# hd-hdr.net
KiCad netlist of a schematic drawn in EAGLE
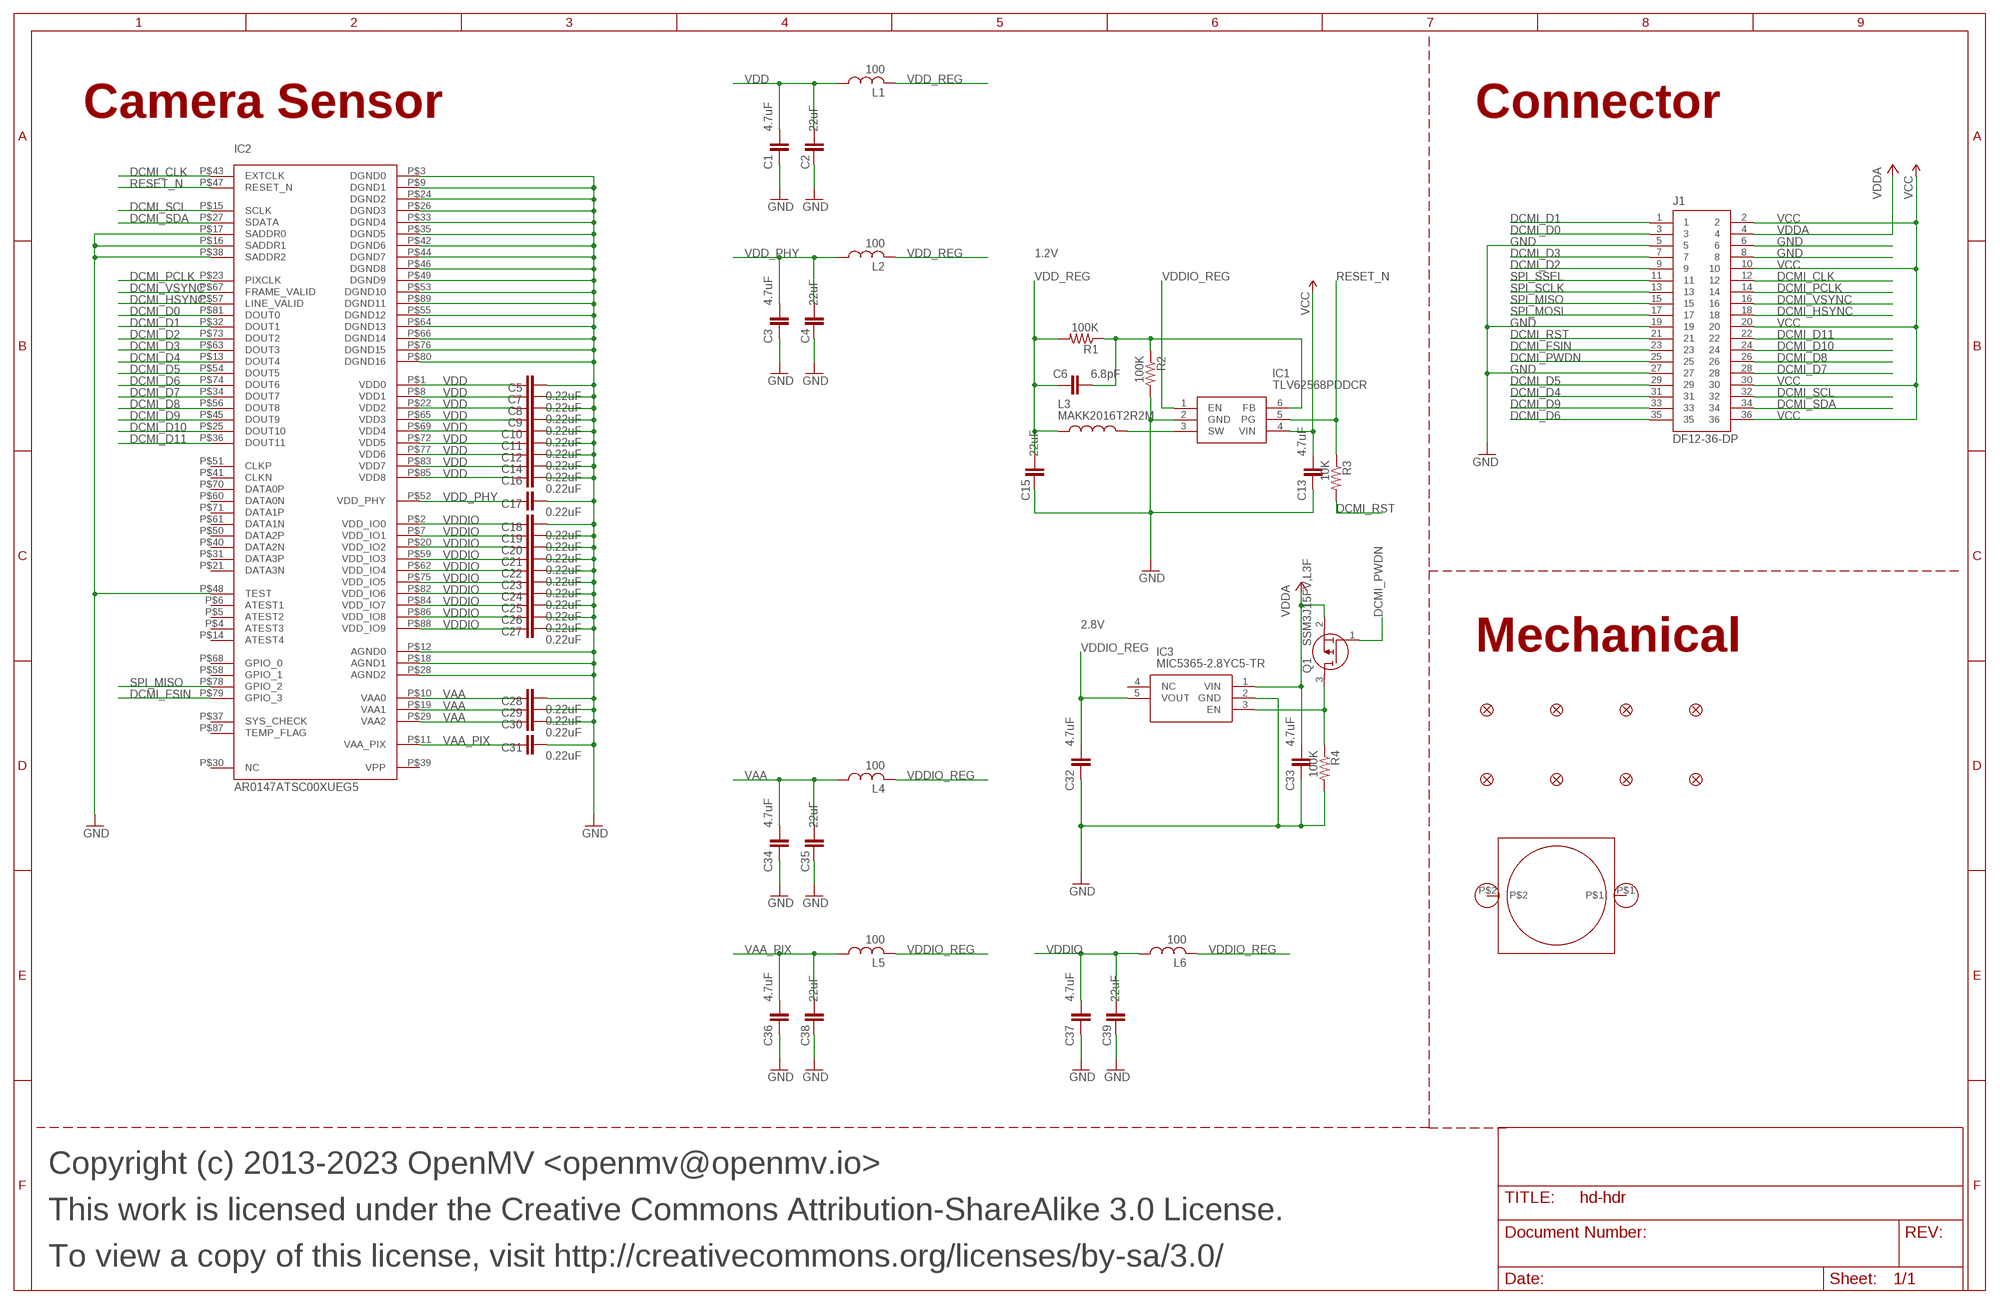
[diagram p0: schematic, sheet 1]

(export (version "E")
  (design (tool "Eeschema 10.0.6"))
  (components
    (comp (ref "C1")
      (value "4.7uF")
      (footprint "eagle-import:0402")
      (fields (field (name "MPN") "JMK105BBJ475MV-F"))
      (libsource (lib "eagle-import") (part "CAP_0402"))
    )
    (comp (ref "C2")
      (value "22uF")
      (footprint "eagle-import:0805")
      (fields (field (name "MPN") "CL21A226MQQNNNE"))
      (libsource (lib "eagle-import") (part "22UF-0805-6.3V-20%"))
    )
    (comp (ref "C3")
      (value "4.7uF")
      (footprint "eagle-import:0402")
      (fields (field (name "MPN") "JMK105BBJ475MV-F"))
      (libsource (lib "eagle-import") (part "CAP_0402"))
    )
    (comp (ref "C4")
      (value "22uF")
      (footprint "eagle-import:0805")
      (fields (field (name "MPN") "CL21A226MQQNNNE"))
      (libsource (lib "eagle-import") (part "22UF-0805-6.3V-20%"))
    )
    (comp (ref "C5")
      (value "0.22uF")
      (footprint "eagle-import:C0201")
      (fields (field (name "MPN") "GRM033R60J224ME15D"))
      (libsource (lib "eagle-import") (part "C-EUC0201"))
    )
    (comp (ref "C6")
      (value "6.8pF")
      (footprint "eagle-import:0402")
      (fields (field (name "MPN") "GRM1555C1H6R8DA01D"))
      (libsource (lib "eagle-import") (part "CAP_0402"))
    )
    (comp (ref "C7")
      (value "0.22uF")
      (footprint "eagle-import:C0201")
      (fields (field (name "MPN") "GRM033R60J224ME15D"))
      (libsource (lib "eagle-import") (part "C-EUC0201"))
    )
    (comp (ref "C8")
      (value "0.22uF")
      (footprint "eagle-import:C0201")
      (fields (field (name "MPN") "GRM033R60J224ME15D"))
      (libsource (lib "eagle-import") (part "C-EUC0201"))
    )
    (comp (ref "C9")
      (value "0.22uF")
      (footprint "eagle-import:C0201")
      (fields (field (name "MPN") "GRM033R60J224ME15D"))
      (libsource (lib "eagle-import") (part "C-EUC0201"))
    )
    (comp (ref "C10")
      (value "0.22uF")
      (footprint "eagle-import:C0201")
      (fields (field (name "MPN") "GRM033R60J224ME15D"))
      (libsource (lib "eagle-import") (part "C-EUC0201"))
    )
    (comp (ref "C11")
      (value "0.22uF")
      (footprint "eagle-import:C0201")
      (fields (field (name "MPN") "GRM033R60J224ME15D"))
      (libsource (lib "eagle-import") (part "C-EUC0201"))
    )
    (comp (ref "C12")
      (value "0.22uF")
      (footprint "eagle-import:C0201")
      (fields (field (name "MPN") "GRM033R60J224ME15D"))
      (libsource (lib "eagle-import") (part "C-EUC0201"))
    )
    (comp (ref "C13")
      (value "4.7uF")
      (footprint "eagle-import:0402")
      (fields (field (name "MPN") "JMK105BBJ475MV-F"))
      (libsource (lib "eagle-import") (part "CAP_0402"))
    )
    (comp (ref "C14")
      (value "0.22uF")
      (footprint "eagle-import:C0201")
      (fields (field (name "MPN") "GRM033R60J224ME15D"))
      (libsource (lib "eagle-import") (part "C-EUC0201"))
    )
    (comp (ref "C15")
      (value "22uF")
      (footprint "eagle-import:0805")
      (fields (field (name "MPN") "CL21A226MQQNNNE"))
      (libsource (lib "eagle-import") (part "22UF-0805-6.3V-20%"))
    )
    (comp (ref "C16")
      (value "0.22uF")
      (footprint "eagle-import:C0201")
      (fields (field (name "MPN") "GRM033R60J224ME15D"))
      (libsource (lib "eagle-import") (part "C-EUC0201"))
    )
    (comp (ref "C17")
      (value "0.22uF")
      (footprint "eagle-import:C0201")
      (fields (field (name "MPN") "GRM033R60J224ME15D"))
      (libsource (lib "eagle-import") (part "C-EUC0201"))
    )
    (comp (ref "C18")
      (value "0.22uF")
      (footprint "eagle-import:C0201")
      (fields (field (name "MPN") "GRM033R60J224ME15D"))
      (libsource (lib "eagle-import") (part "C-EUC0201"))
    )
    (comp (ref "C19")
      (value "0.22uF")
      (footprint "eagle-import:C0201")
      (fields (field (name "MPN") "GRM033R60J224ME15D"))
      (libsource (lib "eagle-import") (part "C-EUC0201"))
    )
    (comp (ref "C20")
      (value "0.22uF")
      (footprint "eagle-import:C0201")
      (fields (field (name "MPN") "GRM033R60J224ME15D"))
      (libsource (lib "eagle-import") (part "C-EUC0201"))
    )
    (comp (ref "C21")
      (value "0.22uF")
      (footprint "eagle-import:C0201")
      (fields (field (name "MPN") "GRM033R60J224ME15D"))
      (libsource (lib "eagle-import") (part "C-EUC0201"))
    )
    (comp (ref "C22")
      (value "0.22uF")
      (footprint "eagle-import:C0201")
      (fields (field (name "MPN") "GRM033R60J224ME15D"))
      (libsource (lib "eagle-import") (part "C-EUC0201"))
    )
    (comp (ref "C23")
      (value "0.22uF")
      (footprint "eagle-import:C0201")
      (fields (field (name "MPN") "GRM033R60J224ME15D"))
      (libsource (lib "eagle-import") (part "C-EUC0201"))
    )
    (comp (ref "C24")
      (value "0.22uF")
      (footprint "eagle-import:C0201")
      (fields (field (name "MPN") "GRM033R60J224ME15D"))
      (libsource (lib "eagle-import") (part "C-EUC0201"))
    )
    (comp (ref "C25")
      (value "0.22uF")
      (footprint "eagle-import:C0201")
      (fields (field (name "MPN") "GRM033R60J224ME15D"))
      (libsource (lib "eagle-import") (part "C-EUC0201"))
    )
    (comp (ref "C26")
      (value "0.22uF")
      (footprint "eagle-import:C0201")
      (fields (field (name "MPN") "GRM033R60J224ME15D"))
      (libsource (lib "eagle-import") (part "C-EUC0201"))
    )
    (comp (ref "C27")
      (value "0.22uF")
      (footprint "eagle-import:C0201")
      (fields (field (name "MPN") "GRM033R60J224ME15D"))
      (libsource (lib "eagle-import") (part "C-EUC0201"))
    )
    (comp (ref "C28")
      (value "0.22uF")
      (footprint "eagle-import:C0201")
      (fields (field (name "MPN") "GRM033R60J224ME15D"))
      (libsource (lib "eagle-import") (part "C-EUC0201"))
    )
    (comp (ref "C29")
      (value "0.22uF")
      (footprint "eagle-import:C0201")
      (fields (field (name "MPN") "GRM033R60J224ME15D"))
      (libsource (lib "eagle-import") (part "C-EUC0201"))
    )
    (comp (ref "C30")
      (value "0.22uF")
      (footprint "eagle-import:C0201")
      (fields (field (name "MPN") "GRM033R60J224ME15D"))
      (libsource (lib "eagle-import") (part "C-EUC0201"))
    )
    (comp (ref "C31")
      (value "0.22uF")
      (footprint "eagle-import:C0201")
      (fields (field (name "MPN") "GRM033R60J224ME15D"))
      (libsource (lib "eagle-import") (part "C-EUC0201"))
    )
    (comp (ref "C32")
      (value "4.7uF")
      (footprint "eagle-import:0402")
      (fields (field (name "MPN") "JMK105BBJ475MV-F"))
      (libsource (lib "eagle-import") (part "CAP_0402"))
    )
    (comp (ref "C33")
      (value "4.7uF")
      (footprint "eagle-import:0402")
      (fields (field (name "MPN") "JMK105BBJ475MV-F"))
      (libsource (lib "eagle-import") (part "CAP_0402"))
    )
    (comp (ref "C34")
      (value "4.7uF")
      (footprint "eagle-import:0402")
      (fields (field (name "MPN") "JMK105BBJ475MV-F"))
      (libsource (lib "eagle-import") (part "CAP_0402"))
    )
    (comp (ref "C35")
      (value "22uF")
      (footprint "eagle-import:0805")
      (fields (field (name "MPN") "CL21A226MQQNNNE"))
      (libsource (lib "eagle-import") (part "22UF-0805-6.3V-20%"))
    )
    (comp (ref "C36")
      (value "4.7uF")
      (footprint "eagle-import:0402")
      (fields (field (name "MPN") "JMK105BBJ475MV-F"))
      (libsource (lib "eagle-import") (part "CAP_0402"))
    )
    (comp (ref "C37")
      (value "4.7uF")
      (footprint "eagle-import:0402")
      (fields (field (name "MPN") "JMK105BBJ475MV-F"))
      (libsource (lib "eagle-import") (part "CAP_0402"))
    )
    (comp (ref "C38")
      (value "22uF")
      (footprint "eagle-import:0805")
      (fields (field (name "MPN") "CL21A226MQQNNNE"))
      (libsource (lib "eagle-import") (part "22UF-0805-6.3V-20%"))
    )
    (comp (ref "C39")
      (value "22uF")
      (footprint "eagle-import:0805")
      (fields (field (name "MPN") "CL21A226MQQNNNE"))
      (libsource (lib "eagle-import") (part "22UF-0805-6.3V-20%"))
    )
    (comp (ref "FD1")
      (value "FIDUCIAL1X2")
      (footprint "eagle-import:FIDUCIAL-1X2")
      (libsource (lib "eagle-import") (part "FIDUCIAL1X2"))
    )
    (comp (ref "FD2")
      (value "FIDUCIAL1X2")
      (footprint "eagle-import:FIDUCIAL-1X2")
      (libsource (lib "eagle-import") (part "FIDUCIAL1X2"))
    )
    (comp (ref "FD3")
      (value "FIDUCIAL1X2")
      (footprint "eagle-import:FIDUCIAL-1X2")
      (libsource (lib "eagle-import") (part "FIDUCIAL1X2"))
    )
    (comp (ref "FD4")
      (value "FIDUCIAL1X2")
      (footprint "eagle-import:FIDUCIAL-1X2")
      (libsource (lib "eagle-import") (part "FIDUCIAL1X2"))
    )
    (comp (ref "FD5")
      (value "FIDUCIAL1X2")
      (footprint "eagle-import:FIDUCIAL-1X2")
      (libsource (lib "eagle-import") (part "FIDUCIAL1X2"))
    )
    (comp (ref "FD6")
      (value "FIDUCIAL1X2")
      (footprint "eagle-import:FIDUCIAL-1X2")
      (libsource (lib "eagle-import") (part "FIDUCIAL1X2"))
    )
    (comp (ref "FD7")
      (value "FIDUCIAL1X2")
      (footprint "eagle-import:FIDUCIAL-1X2")
      (libsource (lib "eagle-import") (part "FIDUCIAL1X2"))
    )
    (comp (ref "FD8")
      (value "FIDUCIAL1X2")
      (footprint "eagle-import:FIDUCIAL-1X2")
      (libsource (lib "eagle-import") (part "FIDUCIAL1X2"))
    )
    (comp (ref "H1")
      (value "LENSMOUNT20MM")
      (footprint "eagle-import:LENSMOUNT-20MM")
      (libsource (lib "eagle-import") (part "LENSMOUNT20MM"))
    )
    (comp (ref "IC1")
      (value "TLV62568PDDCR")
      (footprint "eagle-import:SOT95P280X110-6N")
      (fields (field (name "MOUSER_PART_NUMBER") "595-TLV62568PDDCR"))
      (libsource (lib "eagle-import") (part "TLV62568PDDCR"))
    )
    (comp (ref "IC2")
      (value "AR0147ATSC00XUEG5")
      (footprint "eagle-import:AR0147ATSC00XUEG5")
      (fields (field (name "MPN") "AR0147ATSC00XUEG5-DRBR"))
      (libsource (lib "eagle-import") (part "AR0147ATSC00XUEG5"))
    )
    (comp (ref "IC3")
      (value "MIC5365-2.8YC5-TR")
      (footprint "eagle-import:SOT65P210X110-5N")
      (fields (field (name "MOUSER_PART_NUMBER") "998-MIC5365-2.8YC5TR"))
      (libsource (lib "eagle-import") (part "MIC5365-2.8YC5-TR"))
    )
    (comp (ref "J1")
      (value "DF12-36-DP")
      (footprint "eagle-import:DF12-36-DP")
      (fields (field (name "MPN") "DF12NB(3.0)-36DP-0.5V(51)"))
      (libsource (lib "eagle-import") (part "DF12-36-DP"))
    )
    (comp (ref "L1")
      (value "100")
      (footprint "eagle-import:0402")
      (fields (field (name "MPN") "MFBM1V1005-101-R"))
      (libsource (lib "eagle-import") (part "INDUCTOR_0402"))
    )
    (comp (ref "L2")
      (value "100")
      (footprint "eagle-import:0402")
      (fields (field (name "MPN") "MFBM1V1005-101-R"))
      (libsource (lib "eagle-import") (part "INDUCTOR_0402"))
    )
    (comp (ref "L3")
      (value "MAKK2016T2R2M")
      (footprint "eagle-import:INDC2016X100N")
      (fields (field (name "MF") "Taiyo Yuden"))
      (libsource (lib "eagle-import") (part "MAKK2016T2R2M"))
    )
    (comp (ref "L4")
      (value "100")
      (footprint "eagle-import:0402")
      (fields (field (name "MPN") "MFBM1V1005-101-R"))
      (libsource (lib "eagle-import") (part "INDUCTOR_0402"))
    )
    (comp (ref "L5")
      (value "100")
      (footprint "eagle-import:0402")
      (fields (field (name "MPN") "MFBM1V1005-101-R"))
      (libsource (lib "eagle-import") (part "INDUCTOR_0402"))
    )
    (comp (ref "L6")
      (value "100")
      (footprint "eagle-import:0402")
      (fields (field (name "MPN") "MFBM1V1005-101-R"))
      (libsource (lib "eagle-import") (part "INDUCTOR_0402"))
    )
    (comp (ref "Q1")
      (value "SSM3J15FV,L3F")
      (footprint "eagle-import:SSM3J15FVL3F")
      (fields (field (name "MOUSER_PART_NUMBER") "757-SSM3J15FVL3F"))
      (libsource (lib "eagle-import") (part "SSM3J15FV,L3F"))
    )
    (comp (ref "R1")
      (value "100K")
      (footprint "eagle-import:R0402")
      (fields (field (name "MPN") "AC0402FR-07100KL"))
      (libsource (lib "eagle-import") (part "R-US_R0402"))
    )
    (comp (ref "R2")
      (value "100K")
      (footprint "eagle-import:R0402")
      (fields (field (name "MPN") "AC0402FR-07100KL"))
      (libsource (lib "eagle-import") (part "R-US_R0402"))
    )
    (comp (ref "R3")
      (value "10K")
      (footprint "eagle-import:R0402")
      (fields (field (name "MPN") "AC0402FR-1310KL"))
      (libsource (lib "eagle-import") (part "R-US_R0402"))
    )
    (comp (ref "R4")
      (value "100K")
      (footprint "eagle-import:R0402")
      (fields (field (name "MPN") "AC0402FR-07100KL"))
      (libsource (lib "eagle-import") (part "R-US_R0402"))
    )
  )
  (nets
    (net (code "1") (name "/DCMI_CLK") (class "Default")
      (node (ref "IC2") (pin "P$43") (pinfunction "EXTCLK_P$43") (pintype "bidirectional"))
      (node (ref "J1") (pin "12") (pinfunction "12_12") (pintype "bidirectional"))
    )
    (net (code "2") (name "/DCMI_D0") (class "Default")
      (node (ref "IC2") (pin "P$81") (pinfunction "DOUT0_P$81") (pintype "bidirectional"))
      (node (ref "J1") (pin "3") (pinfunction "3_3") (pintype "bidirectional"))
    )
    (net (code "3") (name "/DCMI_D1") (class "Default")
      (node (ref "IC2") (pin "P$32") (pinfunction "DOUT1_P$32") (pintype "bidirectional"))
      (node (ref "J1") (pin "1") (pinfunction "1_1") (pintype "bidirectional"))
    )
    (net (code "4") (name "/DCMI_D2") (class "Default")
      (node (ref "IC2") (pin "P$73") (pinfunction "DOUT2_P$73") (pintype "bidirectional"))
      (node (ref "J1") (pin "9") (pinfunction "9_9") (pintype "bidirectional"))
    )
    (net (code "5") (name "/DCMI_D3") (class "Default")
      (node (ref "IC2") (pin "P$63") (pinfunction "DOUT3_P$63") (pintype "bidirectional"))
      (node (ref "J1") (pin "7") (pinfunction "7_7") (pintype "bidirectional"))
    )
    (net (code "6") (name "/DCMI_D4") (class "Default")
      (node (ref "IC2") (pin "P$13") (pinfunction "DOUT4_P$13") (pintype "bidirectional"))
      (node (ref "J1") (pin "31") (pinfunction "31_31") (pintype "bidirectional"))
    )
    (net (code "7") (name "/DCMI_D5") (class "Default")
      (node (ref "IC2") (pin "P$54") (pinfunction "DOUT5_P$54") (pintype "bidirectional"))
      (node (ref "J1") (pin "29") (pinfunction "29_29") (pintype "bidirectional"))
    )
    (net (code "8") (name "/DCMI_D6") (class "Default")
      (node (ref "IC2") (pin "P$74") (pinfunction "DOUT6_P$74") (pintype "bidirectional"))
      (node (ref "J1") (pin "35") (pinfunction "35_35") (pintype "bidirectional"))
    )
    (net (code "9") (name "/DCMI_D7") (class "Default")
      (node (ref "IC2") (pin "P$34") (pinfunction "DOUT7_P$34") (pintype "bidirectional"))
      (node (ref "J1") (pin "28") (pinfunction "28_28") (pintype "bidirectional"))
    )
    (net (code "10") (name "/DCMI_D8") (class "Default")
      (node (ref "IC2") (pin "P$56") (pinfunction "DOUT8_P$56") (pintype "bidirectional"))
      (node (ref "J1") (pin "26") (pinfunction "26_26") (pintype "bidirectional"))
    )
    (net (code "11") (name "/DCMI_D9") (class "Default")
      (node (ref "IC2") (pin "P$45") (pinfunction "DOUT9_P$45") (pintype "bidirectional"))
      (node (ref "J1") (pin "33") (pinfunction "33_33") (pintype "bidirectional"))
    )
    (net (code "12") (name "/DCMI_D10") (class "Default")
      (node (ref "IC2") (pin "P$25") (pinfunction "DOUT10_P$25") (pintype "bidirectional"))
      (node (ref "J1") (pin "24") (pinfunction "24_24") (pintype "bidirectional"))
    )
    (net (code "13") (name "/DCMI_D11") (class "Default")
      (node (ref "IC2") (pin "P$36") (pinfunction "DOUT11_P$36") (pintype "bidirectional"))
      (node (ref "J1") (pin "22") (pinfunction "22_22") (pintype "bidirectional"))
    )
    (net (code "14") (name "/DCMI_FSIN") (class "Default")
      (node (ref "IC2") (pin "P$79") (pinfunction "GPIO_3_P$79") (pintype "bidirectional"))
      (node (ref "J1") (pin "23") (pinfunction "23_23") (pintype "bidirectional"))
    )
    (net (code "15") (name "/DCMI_HSYNC") (class "Default")
      (node (ref "IC2") (pin "P$57") (pinfunction "LINE_VALID_P$57") (pintype "bidirectional"))
      (node (ref "J1") (pin "18") (pinfunction "18_18") (pintype "bidirectional"))
    )
    (net (code "16") (name "/DCMI_PCLK") (class "Default")
      (node (ref "IC2") (pin "P$23") (pinfunction "PIXCLK_P$23") (pintype "bidirectional"))
      (node (ref "J1") (pin "14") (pinfunction "14_14") (pintype "bidirectional"))
    )
    (net (code "17") (name "/DCMI_PWDN") (class "Default")
      (node (ref "J1") (pin "25") (pinfunction "25_25") (pintype "bidirectional"))
      (node (ref "Q1") (pin "1") (pinfunction "G_1") (pintype "bidirectional"))
    )
    (net (code "18") (name "/DCMI_RST") (class "Default")
      (node (ref "J1") (pin "21") (pinfunction "21_21") (pintype "bidirectional"))
      (node (ref "R3") (pin "2") (pinfunction "2_2") (pintype "passive"))
    )
    (net (code "19") (name "/DCMI_SCL") (class "Default")
      (node (ref "IC2") (pin "P$15") (pinfunction "SCLK_P$15") (pintype "bidirectional"))
      (node (ref "J1") (pin "32") (pinfunction "32_32") (pintype "bidirectional"))
    )
    (net (code "20") (name "/DCMI_SDA") (class "Default")
      (node (ref "IC2") (pin "P$27") (pinfunction "SDATA_P$27") (pintype "bidirectional"))
      (node (ref "J1") (pin "34") (pinfunction "34_34") (pintype "bidirectional"))
    )
    (net (code "21") (name "/DCMI_VSYNC") (class "Default")
      (node (ref "IC2") (pin "P$67") (pinfunction "FRAME_VALID_P$67") (pintype "bidirectional"))
      (node (ref "J1") (pin "16") (pinfunction "16_16") (pintype "bidirectional"))
    )
    (net (code "22") (name "/P$1") (class "Default")
      (node (ref "H1") (pin "P$1") (pinfunction "P$1_P$1") (pintype "power_in"))
    )
    (net (code "23") (name "/P$2") (class "Default")
      (node (ref "H1") (pin "P$2") (pinfunction "P$2_P$2") (pintype "power_in"))
    )
    (net (code "24") (name "/RESET_N") (class "Default")
      (node (ref "IC1") (pin "5") (pinfunction "PG_5") (pintype "bidirectional"))
      (node (ref "IC2") (pin "P$47") (pinfunction "RESET_N_P$47") (pintype "bidirectional"))
      (node (ref "R3") (pin "1") (pinfunction "1_1") (pintype "passive"))
    )
    (net (code "25") (name "/SPI_MISO") (class "Default")
      (node (ref "IC2") (pin "P$78") (pinfunction "GPIO_2_P$78") (pintype "bidirectional"))
      (node (ref "J1") (pin "15") (pinfunction "15_15") (pintype "bidirectional"))
    )
    (net (code "26") (name "/SPI_MOSI") (class "Default")
      (node (ref "J1") (pin "17") (pinfunction "17_17") (pintype "bidirectional"))
    )
    (net (code "27") (name "/SPI_SCLK") (class "Default")
      (node (ref "J1") (pin "13") (pinfunction "13_13") (pintype "bidirectional"))
    )
    (net (code "28") (name "/SPI_SSEL") (class "Default")
      (node (ref "J1") (pin "11") (pinfunction "11_11") (pintype "bidirectional"))
    )
    (net (code "29") (name "/VAA") (class "Default")
      (node (ref "C28") (pin "1") (pinfunction "1_1") (pintype "passive"))
      (node (ref "C29") (pin "1") (pinfunction "1_1") (pintype "passive"))
      (node (ref "C30") (pin "1") (pinfunction "1_1") (pintype "passive"))
      (node (ref "C34") (pin "2") (pinfunction "2_2") (pintype "passive"))
      (node (ref "C35") (pin "2") (pinfunction "2_2") (pintype "passive"))
      (node (ref "IC2") (pin "P$10") (pinfunction "VAA0_P$10") (pintype "bidirectional"))
      (node (ref "IC2") (pin "P$19") (pinfunction "VAA1_P$19") (pintype "bidirectional"))
      (node (ref "IC2") (pin "P$29") (pinfunction "VAA2_P$29") (pintype "bidirectional"))
      (node (ref "L4") (pin "1") (pinfunction "P$1_1") (pintype "passive"))
    )
    (net (code "30") (name "/VAA_PIX") (class "Default")
      (node (ref "C31") (pin "1") (pinfunction "1_1") (pintype "passive"))
      (node (ref "C36") (pin "2") (pinfunction "2_2") (pintype "passive"))
      (node (ref "C38") (pin "2") (pinfunction "2_2") (pintype "passive"))
      (node (ref "IC2") (pin "P$11") (pinfunction "VAA_PIX_P$11") (pintype "bidirectional"))
      (node (ref "L5") (pin "1") (pinfunction "P$1_1") (pintype "passive"))
    )
    (net (code "31") (name "/VDD") (class "Default")
      (node (ref "C1") (pin "2") (pinfunction "2_2") (pintype "passive"))
      (node (ref "C10") (pin "1") (pinfunction "1_1") (pintype "passive"))
      (node (ref "C11") (pin "1") (pinfunction "1_1") (pintype "passive"))
      (node (ref "C12") (pin "1") (pinfunction "1_1") (pintype "passive"))
      (node (ref "C14") (pin "1") (pinfunction "1_1") (pintype "passive"))
      (node (ref "C16") (pin "1") (pinfunction "1_1") (pintype "passive"))
      (node (ref "C2") (pin "2") (pinfunction "2_2") (pintype "passive"))
      (node (ref "C5") (pin "1") (pinfunction "1_1") (pintype "passive"))
      (node (ref "C7") (pin "1") (pinfunction "1_1") (pintype "passive"))
      (node (ref "C8") (pin "1") (pinfunction "1_1") (pintype "passive"))
      (node (ref "C9") (pin "1") (pinfunction "1_1") (pintype "passive"))
      (node (ref "IC2") (pin "P$1") (pinfunction "VDD0_P$1") (pintype "bidirectional"))
      (node (ref "IC2") (pin "P$22") (pinfunction "VDD2_P$22") (pintype "bidirectional"))
      (node (ref "IC2") (pin "P$65") (pinfunction "VDD3_P$65") (pintype "bidirectional"))
      (node (ref "IC2") (pin "P$69") (pinfunction "VDD4_P$69") (pintype "bidirectional"))
      (node (ref "IC2") (pin "P$72") (pinfunction "VDD5_P$72") (pintype "bidirectional"))
      (node (ref "IC2") (pin "P$77") (pinfunction "VDD6_P$77") (pintype "bidirectional"))
      (node (ref "IC2") (pin "P$8") (pinfunction "VDD1_P$8") (pintype "bidirectional"))
      (node (ref "IC2") (pin "P$83") (pinfunction "VDD7_P$83") (pintype "bidirectional"))
      (node (ref "IC2") (pin "P$85") (pinfunction "VDD8_P$85") (pintype "bidirectional"))
      (node (ref "L1") (pin "1") (pinfunction "P$1_1") (pintype "passive"))
    )
    (net (code "32") (name "/VDDIO") (class "Default")
      (node (ref "C18") (pin "1") (pinfunction "1_1") (pintype "passive"))
      (node (ref "C19") (pin "1") (pinfunction "1_1") (pintype "passive"))
      (node (ref "C20") (pin "1") (pinfunction "1_1") (pintype "passive"))
      (node (ref "C21") (pin "1") (pinfunction "1_1") (pintype "passive"))
      (node (ref "C22") (pin "1") (pinfunction "1_1") (pintype "passive"))
      (node (ref "C23") (pin "1") (pinfunction "1_1") (pintype "passive"))
      (node (ref "C24") (pin "1") (pinfunction "1_1") (pintype "passive"))
      (node (ref "C25") (pin "1") (pinfunction "1_1") (pintype "passive"))
      (node (ref "C26") (pin "1") (pinfunction "1_1") (pintype "passive"))
      (node (ref "C27") (pin "1") (pinfunction "1_1") (pintype "passive"))
      (node (ref "C37") (pin "2") (pinfunction "2_2") (pintype "passive"))
      (node (ref "C39") (pin "2") (pinfunction "2_2") (pintype "passive"))
      (node (ref "IC2") (pin "P$2") (pinfunction "VDD_IO0_P$2") (pintype "bidirectional"))
      (node (ref "IC2") (pin "P$20") (pinfunction "VDD_IO2_P$20") (pintype "bidirectional"))
      (node (ref "IC2") (pin "P$59") (pinfunction "VDD_IO3_P$59") (pintype "bidirectional"))
      (node (ref "IC2") (pin "P$62") (pinfunction "VDD_IO4_P$62") (pintype "bidirectional"))
      (node (ref "IC2") (pin "P$7") (pinfunction "VDD_IO1_P$7") (pintype "bidirectional"))
      (node (ref "IC2") (pin "P$75") (pinfunction "VDD_IO5_P$75") (pintype "bidirectional"))
      (node (ref "IC2") (pin "P$82") (pinfunction "VDD_IO6_P$82") (pintype "bidirectional"))
      (node (ref "IC2") (pin "P$84") (pinfunction "VDD_IO7_P$84") (pintype "bidirectional"))
      (node (ref "IC2") (pin "P$86") (pinfunction "VDD_IO8_P$86") (pintype "bidirectional"))
      (node (ref "IC2") (pin "P$88") (pinfunction "VDD_IO9_P$88") (pintype "bidirectional"))
      (node (ref "L6") (pin "1") (pinfunction "P$1_1") (pintype "passive"))
    )
    (net (code "33") (name "/VDDIO_REG") (class "Default")
      (node (ref "C32") (pin "2") (pinfunction "2_2") (pintype "passive"))
      (node (ref "IC1") (pin "1") (pinfunction "EN_1") (pintype "bidirectional"))
      (node (ref "IC3") (pin "5") (pinfunction "VOUT_5") (pintype "bidirectional"))
      (node (ref "L4") (pin "2") (pinfunction "P$2_2") (pintype "passive"))
      (node (ref "L5") (pin "2") (pinfunction "P$2_2") (pintype "passive"))
      (node (ref "L6") (pin "2") (pinfunction "P$2_2") (pintype "passive"))
    )
    (net (code "34") (name "/VDD_PHY") (class "Default")
      (node (ref "C17") (pin "1") (pinfunction "1_1") (pintype "passive"))
      (node (ref "C3") (pin "2") (pinfunction "2_2") (pintype "passive"))
      (node (ref "C4") (pin "2") (pinfunction "2_2") (pintype "passive"))
      (node (ref "IC2") (pin "P$52") (pinfunction "VDD_PHY_P$52") (pintype "bidirectional"))
      (node (ref "L2") (pin "1") (pinfunction "P$1_1") (pintype "passive"))
    )
    (net (code "35") (name "/VDD_REG") (class "Default")
      (node (ref "C15") (pin "2") (pinfunction "2_2") (pintype "passive"))
      (node (ref "C6") (pin "1") (pinfunction "1_1") (pintype "passive"))
      (node (ref "L1") (pin "2") (pinfunction "P$2_2") (pintype "passive"))
      (node (ref "L2") (pin "2") (pinfunction "P$2_2") (pintype "passive"))
      (node (ref "L3") (pin "1") (pinfunction "1_1") (pintype "passive"))
      (node (ref "R1") (pin "2") (pinfunction "2_2") (pintype "passive"))
    )
    (net (code "36") (name "GND") (class "Default")
      (node (ref "C1") (pin "1") (pinfunction "1_1") (pintype "passive"))
      (node (ref "C10") (pin "2") (pinfunction "2_2") (pintype "passive"))
      (node (ref "C11") (pin "2") (pinfunction "2_2") (pintype "passive"))
      (node (ref "C12") (pin "2") (pinfunction "2_2") (pintype "passive"))
      (node (ref "C13") (pin "1") (pinfunction "1_1") (pintype "passive"))
      (node (ref "C14") (pin "2") (pinfunction "2_2") (pintype "passive"))
      (node (ref "C15") (pin "1") (pinfunction "1_1") (pintype "passive"))
      (node (ref "C16") (pin "2") (pinfunction "2_2") (pintype "passive"))
      (node (ref "C17") (pin "2") (pinfunction "2_2") (pintype "passive"))
      (node (ref "C18") (pin "2") (pinfunction "2_2") (pintype "passive"))
      (node (ref "C19") (pin "2") (pinfunction "2_2") (pintype "passive"))
      (node (ref "C2") (pin "1") (pinfunction "1_1") (pintype "passive"))
      (node (ref "C20") (pin "2") (pinfunction "2_2") (pintype "passive"))
      (node (ref "C21") (pin "2") (pinfunction "2_2") (pintype "passive"))
      (node (ref "C22") (pin "2") (pinfunction "2_2") (pintype "passive"))
      (node (ref "C23") (pin "2") (pinfunction "2_2") (pintype "passive"))
      (node (ref "C24") (pin "2") (pinfunction "2_2") (pintype "passive"))
      (node (ref "C25") (pin "2") (pinfunction "2_2") (pintype "passive"))
      (node (ref "C26") (pin "2") (pinfunction "2_2") (pintype "passive"))
      (node (ref "C27") (pin "2") (pinfunction "2_2") (pintype "passive"))
      (node (ref "C28") (pin "2") (pinfunction "2_2") (pintype "passive"))
      (node (ref "C29") (pin "2") (pinfunction "2_2") (pintype "passive"))
      (node (ref "C3") (pin "1") (pinfunction "1_1") (pintype "passive"))
      (node (ref "C30") (pin "2") (pinfunction "2_2") (pintype "passive"))
      (node (ref "C31") (pin "2") (pinfunction "2_2") (pintype "passive"))
      (node (ref "C32") (pin "1") (pinfunction "1_1") (pintype "passive"))
      (node (ref "C33") (pin "1") (pinfunction "1_1") (pintype "passive"))
      (node (ref "C34") (pin "1") (pinfunction "1_1") (pintype "passive"))
      (node (ref "C35") (pin "1") (pinfunction "1_1") (pintype "passive"))
      (node (ref "C36") (pin "1") (pinfunction "1_1") (pintype "passive"))
      (node (ref "C37") (pin "1") (pinfunction "1_1") (pintype "passive"))
      (node (ref "C38") (pin "1") (pinfunction "1_1") (pintype "passive"))
      (node (ref "C39") (pin "1") (pinfunction "1_1") (pintype "passive"))
      (node (ref "C4") (pin "1") (pinfunction "1_1") (pintype "passive"))
      (node (ref "C5") (pin "2") (pinfunction "2_2") (pintype "passive"))
      (node (ref "C7") (pin "2") (pinfunction "2_2") (pintype "passive"))
      (node (ref "C8") (pin "2") (pinfunction "2_2") (pintype "passive"))
      (node (ref "C9") (pin "2") (pinfunction "2_2") (pintype "passive"))
      (node (ref "IC1") (pin "2") (pinfunction "GND_2") (pintype "bidirectional"))
      (node (ref "IC2") (pin "P$12") (pinfunction "AGND0_P$12") (pintype "bidirectional"))
      (node (ref "IC2") (pin "P$16") (pinfunction "SADDR1_P$16") (pintype "bidirectional"))
      (node (ref "IC2") (pin "P$17") (pinfunction "SADDR0_P$17") (pintype "bidirectional"))
      (node (ref "IC2") (pin "P$18") (pinfunction "AGND1_P$18") (pintype "bidirectional"))
      (node (ref "IC2") (pin "P$24") (pinfunction "DGND2_P$24") (pintype "bidirectional"))
      (node (ref "IC2") (pin "P$26") (pinfunction "DGND3_P$26") (pintype "bidirectional"))
      (node (ref "IC2") (pin "P$28") (pinfunction "AGND2_P$28") (pintype "bidirectional"))
      (node (ref "IC2") (pin "P$3") (pinfunction "DGND0_P$3") (pintype "bidirectional"))
      (node (ref "IC2") (pin "P$33") (pinfunction "DGND4_P$33") (pintype "bidirectional"))
      (node (ref "IC2") (pin "P$35") (pinfunction "DGND5_P$35") (pintype "bidirectional"))
      (node (ref "IC2") (pin "P$38") (pinfunction "SADDR2_P$38") (pintype "bidirectional"))
      (node (ref "IC2") (pin "P$42") (pinfunction "DGND6_P$42") (pintype "bidirectional"))
      (node (ref "IC2") (pin "P$44") (pinfunction "DGND7_P$44") (pintype "bidirectional"))
      (node (ref "IC2") (pin "P$46") (pinfunction "DGND8_P$46") (pintype "bidirectional"))
      (node (ref "IC2") (pin "P$48") (pinfunction "TEST_P$48") (pintype "bidirectional"))
      (node (ref "IC2") (pin "P$49") (pinfunction "DGND9_P$49") (pintype "bidirectional"))
      (node (ref "IC2") (pin "P$53") (pinfunction "DGND10_P$53") (pintype "bidirectional"))
      (node (ref "IC2") (pin "P$55") (pinfunction "DGND12_P$55") (pintype "bidirectional"))
      (node (ref "IC2") (pin "P$64") (pinfunction "DGND13_P$64") (pintype "bidirectional"))
      (node (ref "IC2") (pin "P$66") (pinfunction "DGND14_P$66") (pintype "bidirectional"))
      (node (ref "IC2") (pin "P$76") (pinfunction "DGND15_P$76") (pintype "bidirectional"))
      (node (ref "IC2") (pin "P$80") (pinfunction "DGND16_P$80") (pintype "bidirectional"))
      (node (ref "IC2") (pin "P$89") (pinfunction "DGND11_P$89") (pintype "bidirectional"))
      (node (ref "IC2") (pin "P$9") (pinfunction "DGND1_P$9") (pintype "bidirectional"))
      (node (ref "IC3") (pin "2") (pinfunction "GND_2") (pintype "bidirectional"))
      (node (ref "J1") (pin "19") (pinfunction "19_19") (pintype "bidirectional"))
      (node (ref "J1") (pin "27") (pinfunction "27_27") (pintype "bidirectional"))
      (node (ref "J1") (pin "5") (pinfunction "5_5") (pintype "bidirectional"))
      (node (ref "J1") (pin "6") (pinfunction "6_6") (pintype "bidirectional"))
      (node (ref "J1") (pin "8") (pinfunction "8_8") (pintype "bidirectional"))
      (node (ref "R2") (pin "2") (pinfunction "2_2") (pintype "passive"))
      (node (ref "R4") (pin "2") (pinfunction "2_2") (pintype "passive"))
    )
    (net (code "37") (name "Net-(IC1-FB)") (class "Default")
      (node (ref "C6") (pin "2") (pinfunction "2_2") (pintype "passive"))
      (node (ref "IC1") (pin "6") (pinfunction "FB_6") (pintype "bidirectional"))
      (node (ref "R1") (pin "1") (pinfunction "1_1") (pintype "passive"))
      (node (ref "R2") (pin "1") (pinfunction "1_1") (pintype "passive"))
    )
    (net (code "38") (name "Net-(IC1-SW)") (class "Default")
      (node (ref "IC1") (pin "3") (pinfunction "SW_3") (pintype "bidirectional"))
      (node (ref "L3") (pin "2") (pinfunction "2_2") (pintype "passive"))
    )
    (net (code "39") (name "Net-(IC3-EN)") (class "Default")
      (node (ref "IC3") (pin "3") (pinfunction "EN_3") (pintype "bidirectional"))
      (node (ref "Q1") (pin "3") (pinfunction "D_3") (pintype "bidirectional"))
      (node (ref "R4") (pin "1") (pinfunction "1_1") (pintype "passive"))
    )
    (net (code "40") (name "VCC") (class "Default")
      (node (ref "C13") (pin "2") (pinfunction "2_2") (pintype "passive"))
      (node (ref "IC1") (pin "4") (pinfunction "VIN_4") (pintype "bidirectional"))
      (node (ref "J1") (pin "10") (pinfunction "10_10") (pintype "bidirectional"))
      (node (ref "J1") (pin "2") (pinfunction "2_2") (pintype "bidirectional"))
      (node (ref "J1") (pin "20") (pinfunction "20_20") (pintype "bidirectional"))
      (node (ref "J1") (pin "30") (pinfunction "30_30") (pintype "bidirectional"))
      (node (ref "J1") (pin "36") (pinfunction "36_36") (pintype "bidirectional"))
    )
    (net (code "41") (name "VDDA") (class "Default")
      (node (ref "C33") (pin "2") (pinfunction "2_2") (pintype "passive"))
      (node (ref "IC3") (pin "1") (pinfunction "VIN_1") (pintype "bidirectional"))
      (node (ref "J1") (pin "4") (pinfunction "4_4") (pintype "bidirectional"))
      (node (ref "Q1") (pin "2") (pinfunction "S_2") (pintype "bidirectional"))
    )
    (net (code "42") (name "unconnected-(IC2-ATEST1-PadP$6)") (class "Default")
      (node (ref "IC2") (pin "P$6") (pinfunction "ATEST1_P$6") (pintype "bidirectional"))
    )
    (net (code "43") (name "unconnected-(IC2-ATEST2-PadP$5)") (class "Default")
      (node (ref "IC2") (pin "P$5") (pinfunction "ATEST2_P$5") (pintype "bidirectional"))
    )
    (net (code "44") (name "unconnected-(IC2-ATEST3-PadP$4)") (class "Default")
      (node (ref "IC2") (pin "P$4") (pinfunction "ATEST3_P$4") (pintype "bidirectional"))
    )
    (net (code "45") (name "unconnected-(IC2-ATEST4-PadP$14)") (class "Default")
      (node (ref "IC2") (pin "P$14") (pinfunction "ATEST4_P$14") (pintype "bidirectional"))
    )
    (net (code "46") (name "unconnected-(IC2-CLKN-PadP$41)") (class "Default")
      (node (ref "IC2") (pin "P$41") (pinfunction "CLKN_P$41") (pintype "bidirectional"))
    )
    (net (code "47") (name "unconnected-(IC2-CLKP-PadP$51)") (class "Default")
      (node (ref "IC2") (pin "P$51") (pinfunction "CLKP_P$51") (pintype "bidirectional"))
    )
    (net (code "48") (name "unconnected-(IC2-DATA0N-PadP$60)") (class "Default")
      (node (ref "IC2") (pin "P$60") (pinfunction "DATA0N_P$60") (pintype "bidirectional"))
    )
    (net (code "49") (name "unconnected-(IC2-DATA0P-PadP$70)") (class "Default")
      (node (ref "IC2") (pin "P$70") (pinfunction "DATA0P_P$70") (pintype "bidirectional"))
    )
    (net (code "50") (name "unconnected-(IC2-DATA1N-PadP$61)") (class "Default")
      (node (ref "IC2") (pin "P$61") (pinfunction "DATA1N_P$61") (pintype "bidirectional"))
    )
    (net (code "51") (name "unconnected-(IC2-DATA1P-PadP$71)") (class "Default")
      (node (ref "IC2") (pin "P$71") (pinfunction "DATA1P_P$71") (pintype "bidirectional"))
    )
    (net (code "52") (name "unconnected-(IC2-DATA2N-PadP$40)") (class "Default")
      (node (ref "IC2") (pin "P$40") (pinfunction "DATA2N_P$40") (pintype "bidirectional"))
    )
    (net (code "53") (name "unconnected-(IC2-DATA2P-PadP$50)") (class "Default")
      (node (ref "IC2") (pin "P$50") (pinfunction "DATA2P_P$50") (pintype "bidirectional"))
    )
    (net (code "54") (name "unconnected-(IC2-DATA3N-PadP$21)") (class "Default")
      (node (ref "IC2") (pin "P$21") (pinfunction "DATA3N_P$21") (pintype "bidirectional"))
    )
    (net (code "55") (name "unconnected-(IC2-DATA3P-PadP$31)") (class "Default")
      (node (ref "IC2") (pin "P$31") (pinfunction "DATA3P_P$31") (pintype "bidirectional"))
    )
    (net (code "56") (name "unconnected-(IC2-GPIO_0-PadP$68)") (class "Default")
      (node (ref "IC2") (pin "P$68") (pinfunction "GPIO_0_P$68") (pintype "bidirectional"))
    )
    (net (code "57") (name "unconnected-(IC2-GPIO_1-PadP$58)") (class "Default")
      (node (ref "IC2") (pin "P$58") (pinfunction "GPIO_1_P$58") (pintype "bidirectional"))
    )
    (net (code "58") (name "unconnected-(IC2-NC-PadP$30)") (class "Default")
      (node (ref "IC2") (pin "P$30") (pinfunction "NC_P$30") (pintype "bidirectional"))
    )
    (net (code "59") (name "unconnected-(IC2-SYS_CHECK-PadP$37)") (class "Default")
      (node (ref "IC2") (pin "P$37") (pinfunction "SYS_CHECK_P$37") (pintype "bidirectional"))
    )
    (net (code "60") (name "unconnected-(IC2-TEMP_FLAG-PadP$87)") (class "Default")
      (node (ref "IC2") (pin "P$87") (pinfunction "TEMP_FLAG_P$87") (pintype "bidirectional"))
    )
    (net (code "61") (name "unconnected-(IC2-VPP-PadP$39)") (class "Default")
      (node (ref "IC2") (pin "P$39") (pinfunction "VPP_P$39") (pintype "bidirectional"))
    )
    (net (code "62") (name "unconnected-(IC3-NC-Pad4)") (class "Default")
      (node (ref "IC3") (pin "4") (pinfunction "NC_4") (pintype "no_connect"))
    )
  )
)
